# 2DIR_Digital_Isolator.net
KiCad netlist of a schematic drawn in Altium Designer
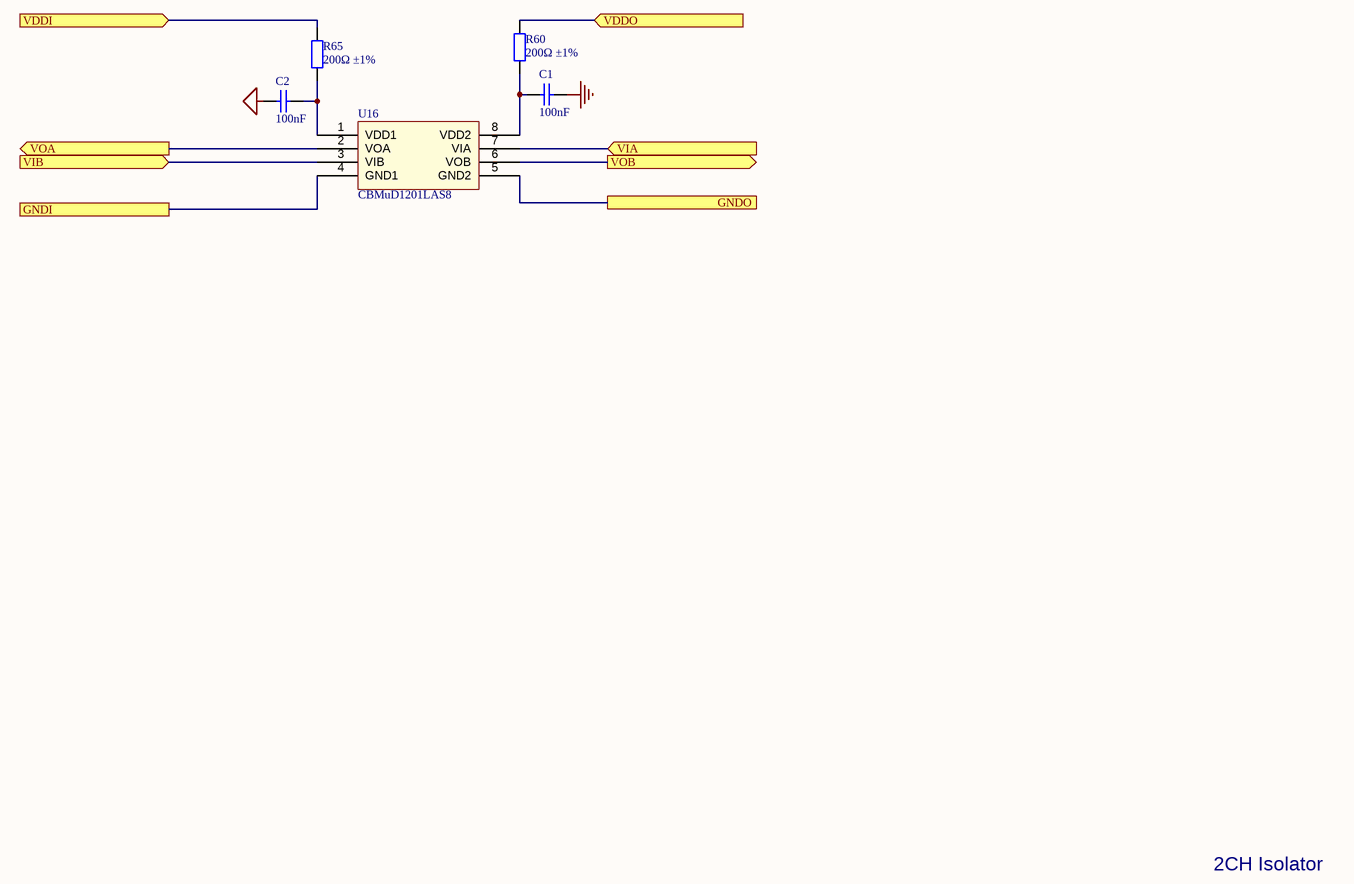
[diagram p0: 2DIR_Digital_Isolator.SchDoc]

(export (version "E")
  (design (tool "Eeschema 10.0.6"))
  (components
    (comp (ref "C1")
      (value "100nF")
      (footprint "0603_C")
      (description "Chip capacitors")
      (fields (field (name "MANUFACTURER") "YAGEO") (field (name "PARTNUMBER") "CC0603KRX7R9BB104"))
      (libsource (lib "Cap") (part "0603 100nF (104) 10% 50V"))
    )
    (comp (ref "C2")
      (value "100nF")
      (footprint "0603_C")
      (description "Chip capacitors")
      (fields (field (name "MANUFACTURER") "YAGEO") (field (name "PARTNUMBER") "CC0603KRX7R9BB104"))
      (libsource (lib "Cap") (part "0603 100nF (104) 10% 50V"))
    )
    (comp (ref "R60")
      (value "200Ω ±1%")
      (footprint "0603_R")
      (description "Chip resistor")
      (fields (field (name "MANUFACTURER") "Uniroyal Elec") (field (name "PARTNUMBER") "0603WAF2000T5E"))
      (libsource (lib "RES") (part "0603 200R (2000) 1%"))
    )
    (comp (ref "R65")
      (value "200Ω ±1%")
      (footprint "0603_R")
      (description "Chip resistor")
      (fields (field (name "MANUFACTURER") "Uniroyal Elec") (field (name "PARTNUMBER") "0603WAF2000T5E"))
      (libsource (lib "RES") (part "0603 200R (2000) 1%"))
    )
    (comp (ref "U16")
      (value "CBMuD1201LAS8")
      (footprint "SOIC-8_150mil")
      (description "Dual Channel Isolator")
      (fields (field (name "MANUFACTURER") "Corebai Microelectronics"))
      (libsource (lib "Sienci_Labs") (part "CBMuD1201LAS8"))
    )
  )
  (nets
    (net (code "1") (name "/GNDI") (class "Default")
      (node (ref "U16") (pin "4") (pinfunction "GND1_4") (pintype "passive"))
    )
    (net (code "2") (name "/GNDO") (class "Default")
      (node (ref "U16") (pin "5") (pinfunction "GND2_5") (pintype "passive"))
    )
    (net (code "3") (name "/VDDI") (class "Default")
      (node (ref "R65") (pin "2") (pinfunction "2_2") (pintype "passive"))
    )
    (net (code "4") (name "/VDDO") (class "Default")
      (node (ref "R60") (pin "2") (pinfunction "2_2") (pintype "passive"))
    )
    (net (code "5") (name "/VIA") (class "Default")
      (node (ref "U16") (pin "7") (pinfunction "VIA_7") (pintype "passive"))
    )
    (net (code "6") (name "/VIB") (class "Default")
      (node (ref "U16") (pin "3") (pinfunction "VIB_3") (pintype "passive"))
    )
    (net (code "7") (name "/VOA") (class "Default")
      (node (ref "U16") (pin "2") (pinfunction "VOA_2") (pintype "passive"))
    )
    (net (code "8") (name "/VOB") (class "Default")
      (node (ref "U16") (pin "6") (pinfunction "VOB_6") (pintype "passive"))
    )
    (net (code "9") (name "GND") (class "Default")
      (node (ref "C1") (pin "1") (pinfunction "1_1") (pintype "passive"))
    )
    (net (code "10") (name "MCU_GND") (class "Default")
      (node (ref "C2") (pin "2") (pinfunction "2_2") (pintype "passive"))
    )
    (net (code "11") (name "Net-(U16-VDD1)") (class "Default")
      (node (ref "C2") (pin "1") (pinfunction "1_1") (pintype "passive"))
      (node (ref "R65") (pin "1") (pinfunction "1_1") (pintype "passive"))
      (node (ref "U16") (pin "1") (pinfunction "VDD1_1") (pintype "passive"))
    )
    (net (code "12") (name "Net-(U16-VDD2)") (class "Default")
      (node (ref "C1") (pin "2") (pinfunction "2_2") (pintype "passive"))
      (node (ref "R60") (pin "1") (pinfunction "1_1") (pintype "passive"))
      (node (ref "U16") (pin "8") (pinfunction "VDD2_8") (pintype "passive"))
    )
  )
)
